# ScouseTom_CS_Shield.net
KiCad netlist of a schematic drawn in EAGLE
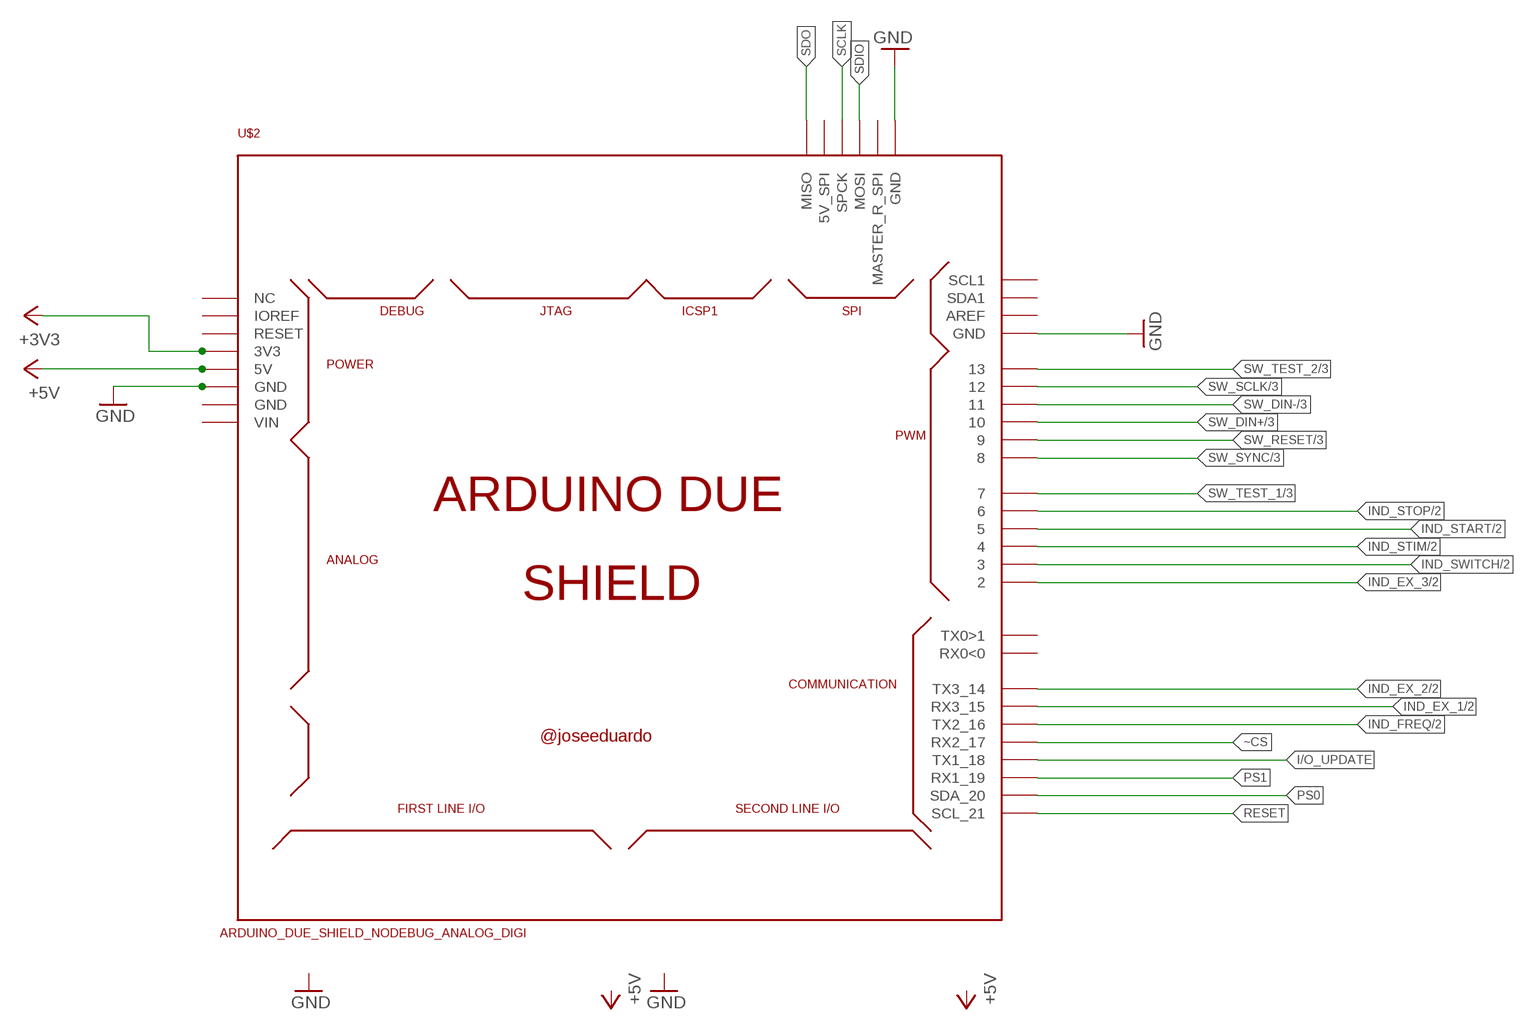
[diagram p0: schematic, sheet 1]
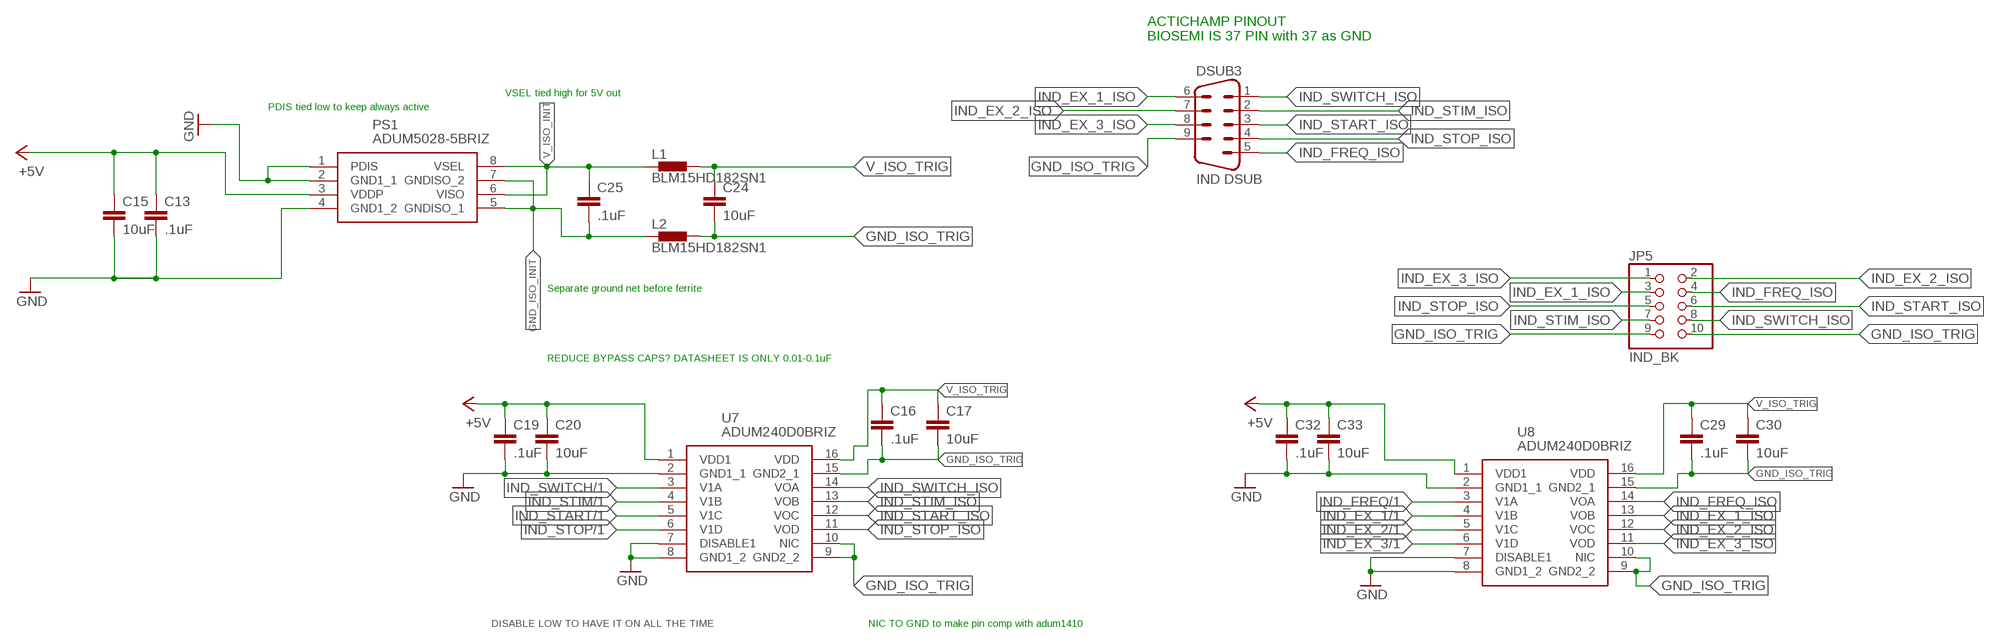
[diagram p1: schematic, sheet 2]
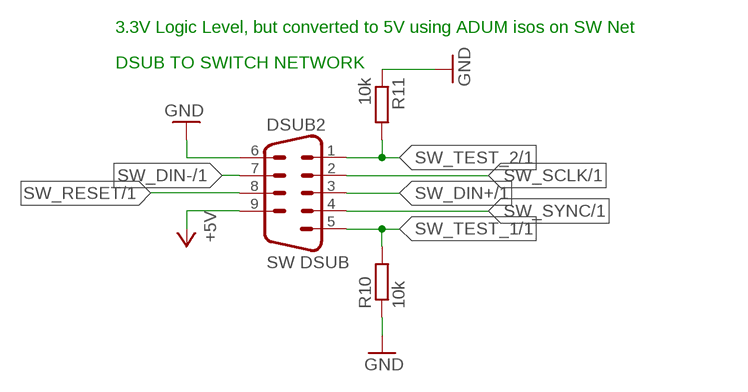
[diagram p2: schematic, sheet 3]
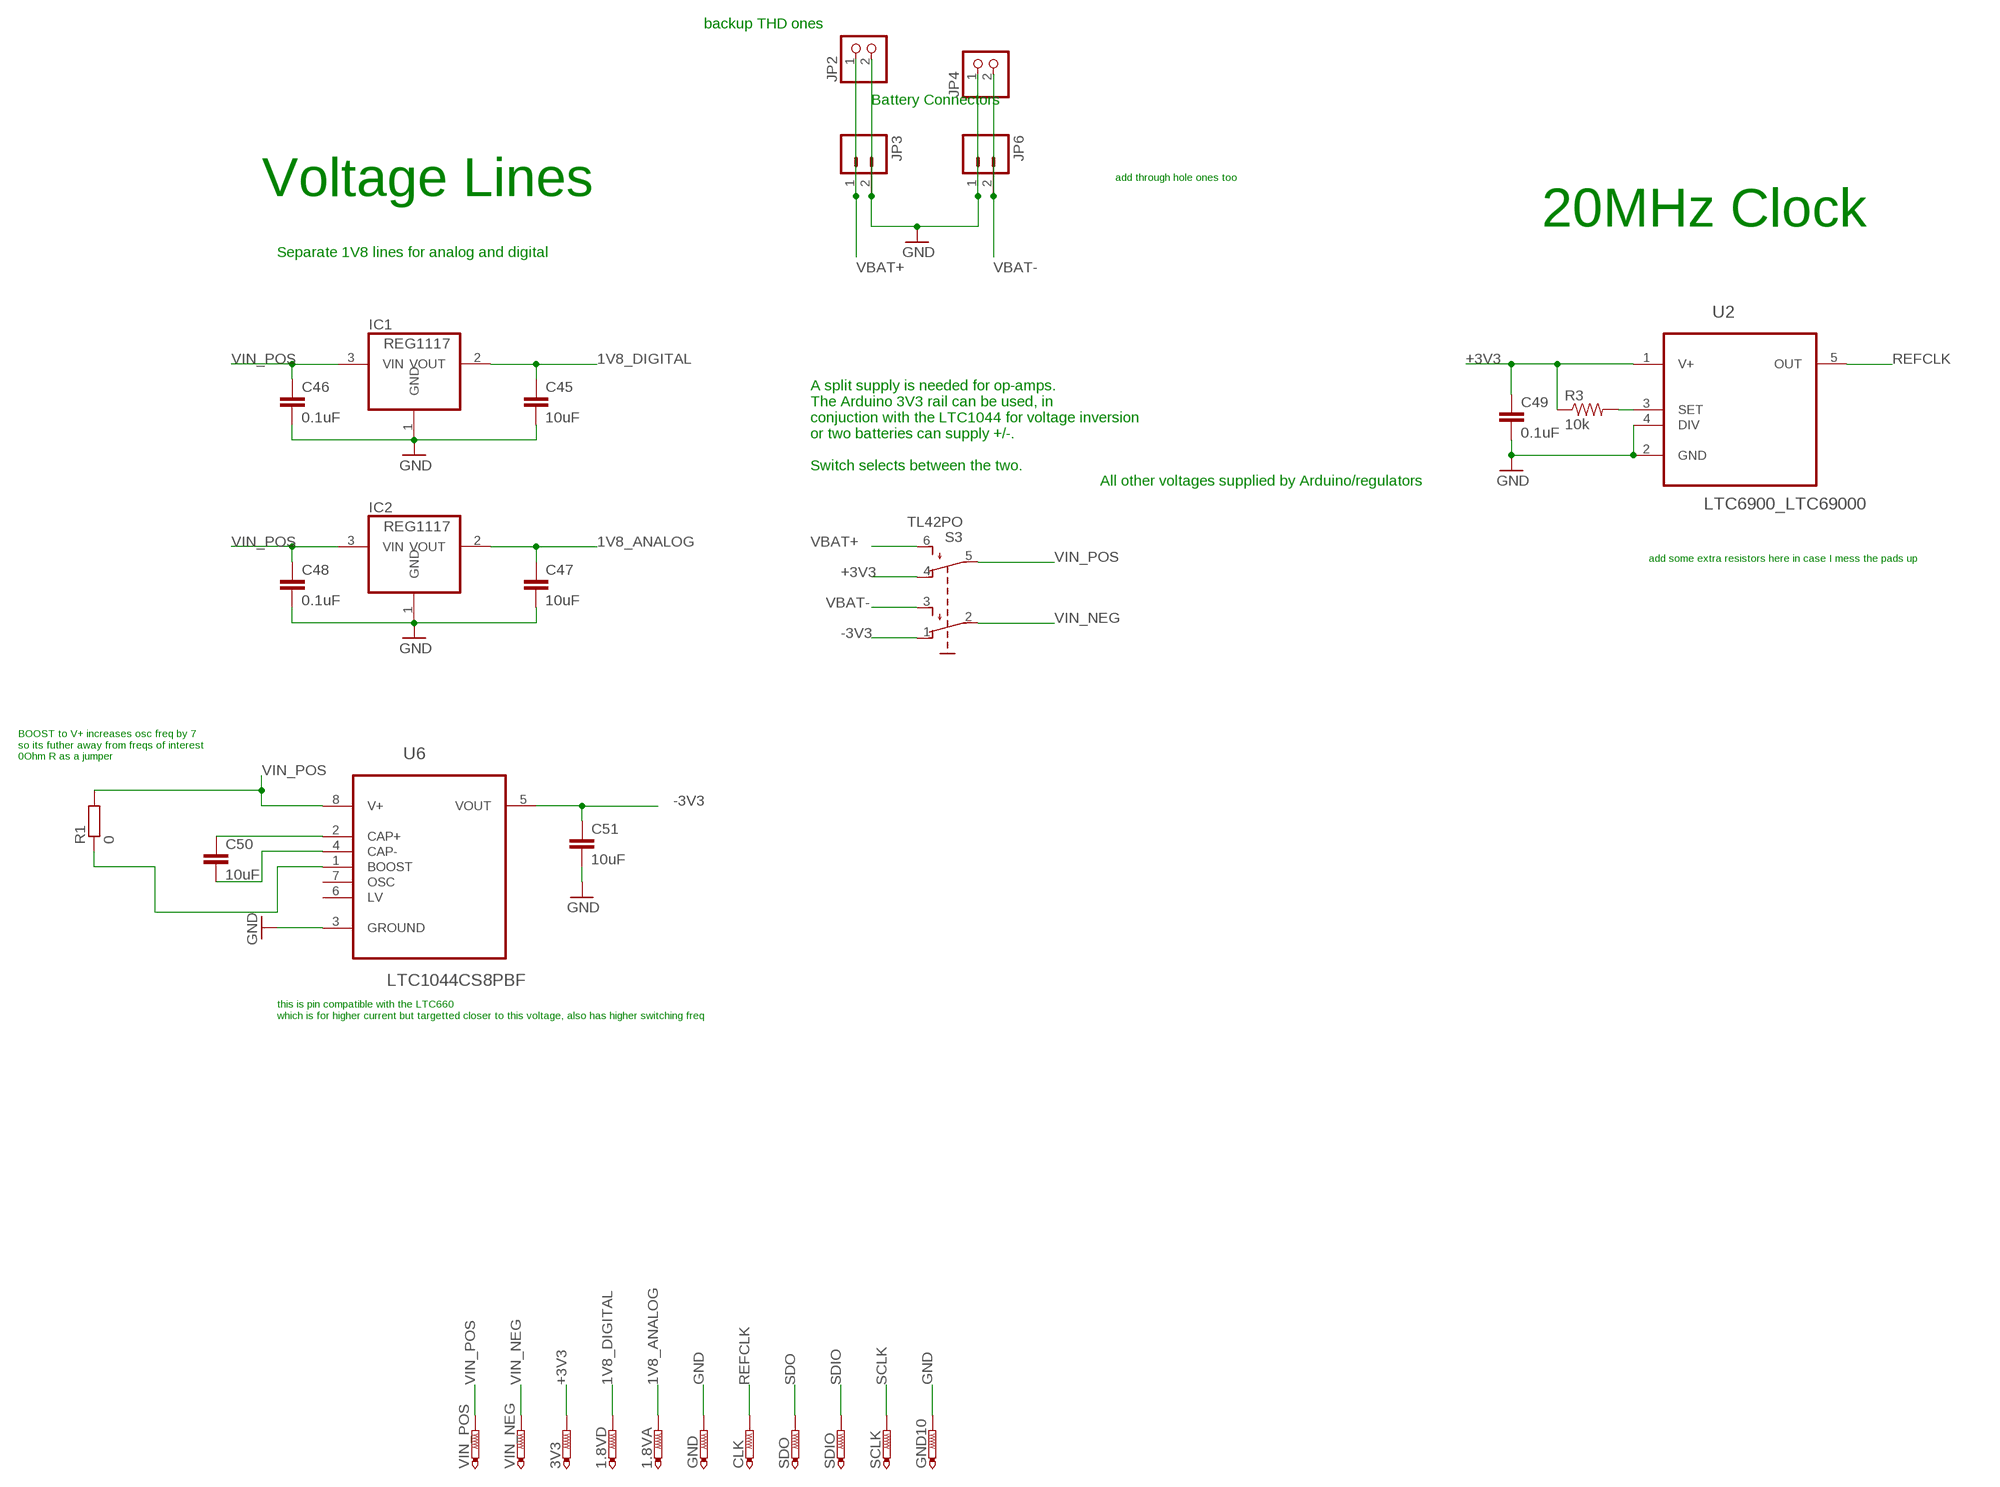
[diagram p3: schematic, sheet 4]
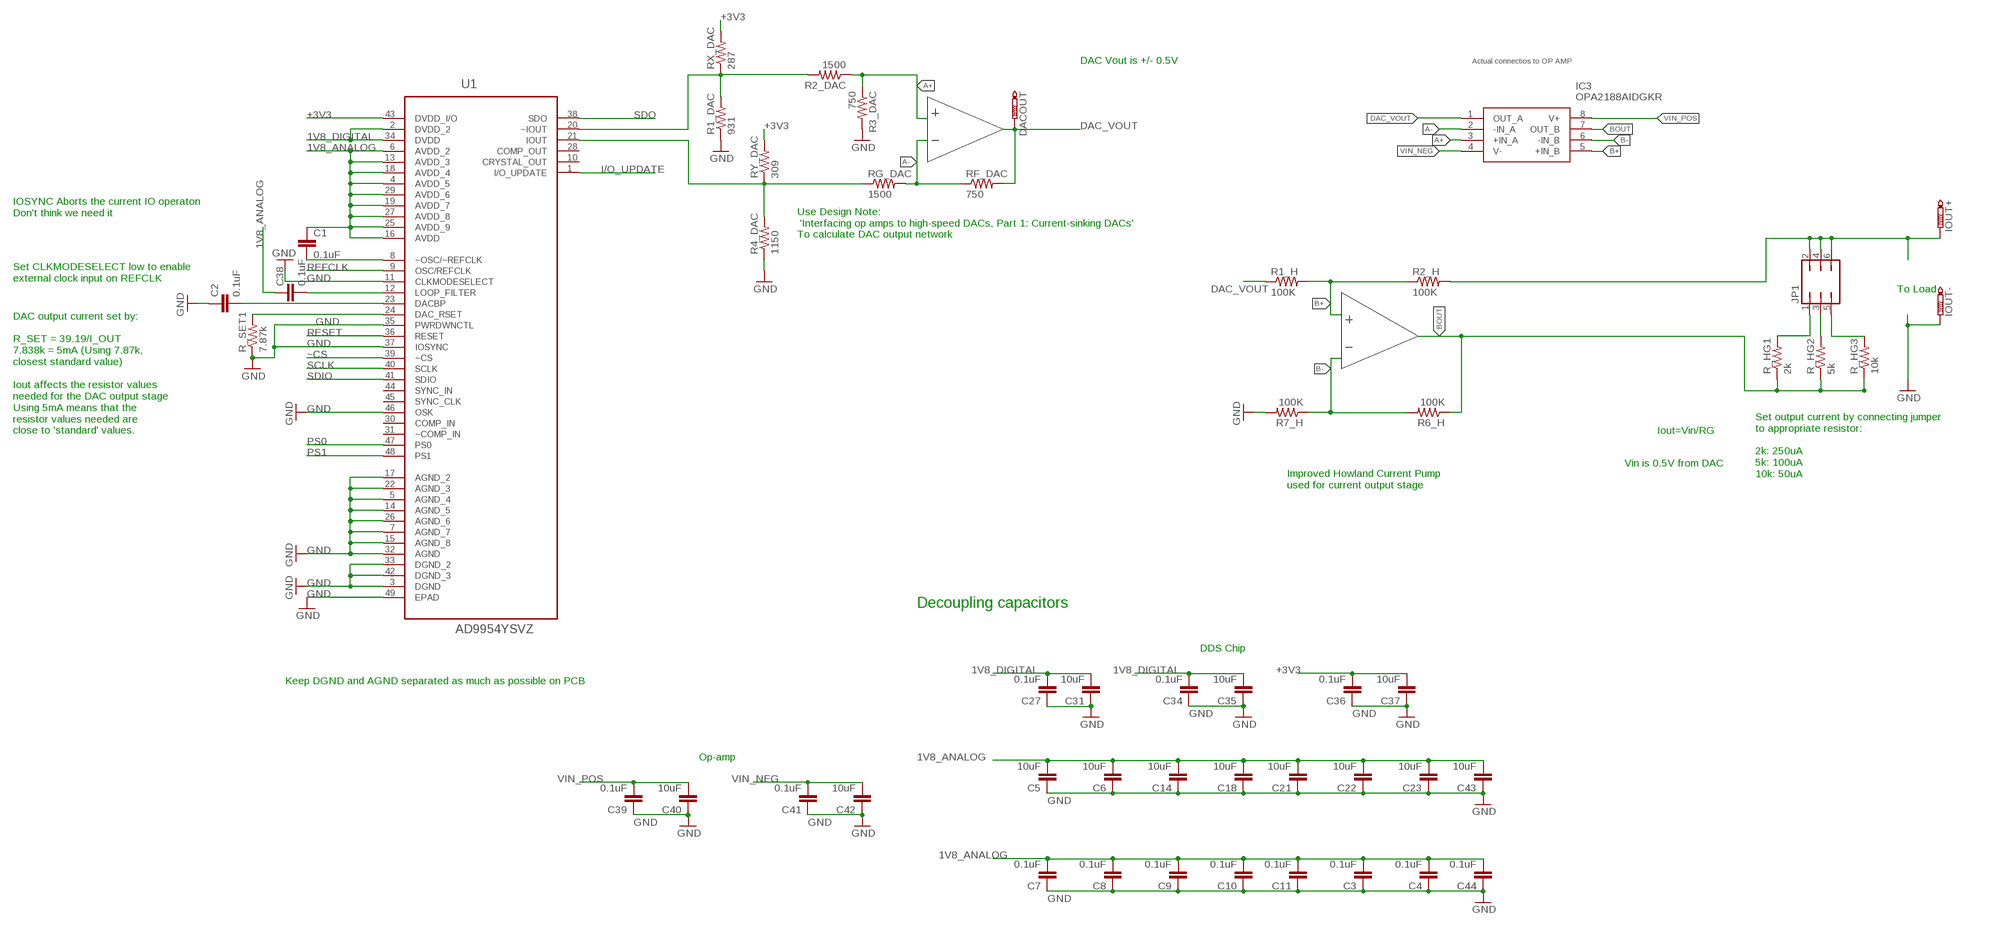
[diagram p4: schematic, sheet 5]

(export (version "E")
  (design (tool "Eeschema 10.0.6"))
  (components
    (comp (ref "U$2")
      (value "ARDUINO_DUE_SHIELD_NODEBUG_ANALOG_DIGI")
      (footprint "eagle-import:ARDUINO_DUE_SHIELD_NODEBUG_ANALOG_DIG")
      (libsource (lib "eagle-import") (part "ARDUINO_DUE_SHIELD_NODEBUG_ANALOG_DIGI"))
    )
    (comp (ref "C13")
      (value ".1uF")
      (footprint "eagle-import:C0603")
      (libsource (lib "eagle-import") (part "C-EUC0603"))
    )
    (comp (ref "C15")
      (value "10uF")
      (footprint "eagle-import:C0603")
      (libsource (lib "eagle-import") (part "C-EUC0603"))
    )
    (comp (ref "C16")
      (value ".1uF")
      (footprint "eagle-import:C0603")
      (libsource (lib "eagle-import") (part "C-EUC0603"))
    )
    (comp (ref "C17")
      (value "10uF")
      (footprint "eagle-import:C0603")
      (libsource (lib "eagle-import") (part "C-EUC0603"))
    )
    (comp (ref "C19")
      (value ".1uF")
      (footprint "eagle-import:C0603")
      (libsource (lib "eagle-import") (part "C-EUC0603"))
    )
    (comp (ref "C20")
      (value "10uF")
      (footprint "eagle-import:C0603")
      (libsource (lib "eagle-import") (part "C-EUC0603"))
    )
    (comp (ref "C24")
      (value "10uF")
      (footprint "eagle-import:C0603")
      (libsource (lib "eagle-import") (part "C-EUC0603"))
    )
    (comp (ref "C25")
      (value ".1uF")
      (footprint "eagle-import:C0603")
      (libsource (lib "eagle-import") (part "C-EUC0603"))
    )
    (comp (ref "C29")
      (value ".1uF")
      (footprint "eagle-import:C0603")
      (libsource (lib "eagle-import") (part "C-EUC0603"))
    )
    (comp (ref "C30")
      (value "10uF")
      (footprint "eagle-import:C0603")
      (libsource (lib "eagle-import") (part "C-EUC0603"))
    )
    (comp (ref "C32")
      (value ".1uF")
      (footprint "eagle-import:C0603")
      (libsource (lib "eagle-import") (part "C-EUC0603"))
    )
    (comp (ref "C33")
      (value "10uF")
      (footprint "eagle-import:C0603")
      (libsource (lib "eagle-import") (part "C-EUC0603"))
    )
    (comp (ref "DSUB3")
      (value "IND DSUB")
      (footprint "eagle-import:DSUB9")
      (libsource (lib "eagle-import") (part "ScouseTom_New_DSUB9RA"))
    )
    (comp (ref "JP5")
      (value "IND_BK")
      (footprint "eagle-import:2X05")
      (libsource (lib "eagle-import") (part "PINHD-2X5"))
    )
    (comp (ref "L1")
      (value "BLM15HD182SN1")
      (footprint "eagle-import:0402")
      (libsource (lib "eagle-import") (part "BLM15HD182SN1"))
    )
    (comp (ref "L2")
      (value "BLM15HD182SN1")
      (footprint "eagle-import:0402")
      (libsource (lib "eagle-import") (part "BLM15HD182SN1"))
    )
    (comp (ref "PS1")
      (value "ADUM5028-5BRIZ")
      (footprint "eagle-import:SOIC127P1031X265-8N")
      (fields (field (name "MOUSER_PART_NUMBER") "584-ADUM5028-5BRIZ"))
      (libsource (lib "eagle-import") (part "ADUM5028-5BRIZ"))
    )
    (comp (ref "U7")
      (value "ADUM240D0BRIZ")
      (footprint "eagle-import:SOIC127P1032X265-16N")
      (libsource (lib "eagle-import") (part "ADUM240D0BRIZ"))
    )
    (comp (ref "U8")
      (value "ADUM240D0BRIZ")
      (footprint "eagle-import:SOIC127P1032X265-16N")
      (libsource (lib "eagle-import") (part "ADUM240D0BRIZ"))
    )
    (comp (ref "C1")
      (value "0.1uF")
      (footprint "eagle-import:C0603")
      (libsource (lib "eagle-import") (part "C-EUC0603"))
    )
    (comp (ref "C2")
      (value "0.1uF")
      (footprint "eagle-import:C0603")
      (libsource (lib "eagle-import") (part "C-EUC0603"))
    )
    (comp (ref "C3")
      (value "0.1uF")
      (footprint "eagle-import:C0603")
      (libsource (lib "eagle-import") (part "C-EUC0603"))
    )
    (comp (ref "C4")
      (value "0.1uF")
      (footprint "eagle-import:C0603")
      (libsource (lib "eagle-import") (part "C-EUC0603"))
    )
    (comp (ref "C5")
      (value "10uF")
      (footprint "eagle-import:C0603")
      (libsource (lib "eagle-import") (part "C-EUC0603"))
    )
    (comp (ref "C6")
      (value "10uF")
      (footprint "eagle-import:C0603")
      (libsource (lib "eagle-import") (part "C-EUC0603"))
    )
    (comp (ref "C7")
      (value "0.1uF")
      (footprint "eagle-import:C0603")
      (libsource (lib "eagle-import") (part "C-EUC0603"))
    )
    (comp (ref "C8")
      (value "0.1uF")
      (footprint "eagle-import:C0603")
      (libsource (lib "eagle-import") (part "C-EUC0603"))
    )
    (comp (ref "C9")
      (value "0.1uF")
      (footprint "eagle-import:C0603")
      (libsource (lib "eagle-import") (part "C-EUC0603"))
    )
    (comp (ref "C10")
      (value "0.1uF")
      (footprint "eagle-import:C0603")
      (libsource (lib "eagle-import") (part "C-EUC0603"))
    )
    (comp (ref "C11")
      (value "0.1uF")
      (footprint "eagle-import:C0603")
      (libsource (lib "eagle-import") (part "C-EUC0603"))
    )
    (comp (ref "C14")
      (value "10uF")
      (footprint "eagle-import:C0603")
      (libsource (lib "eagle-import") (part "C-EUC0603"))
    )
    (comp (ref "C18")
      (value "10uF")
      (footprint "eagle-import:C0603")
      (libsource (lib "eagle-import") (part "C-EUC0603"))
    )
    (comp (ref "C21")
      (value "10uF")
      (footprint "eagle-import:C0603")
      (libsource (lib "eagle-import") (part "C-EUC0603"))
    )
    (comp (ref "C22")
      (value "10uF")
      (footprint "eagle-import:C0603")
      (libsource (lib "eagle-import") (part "C-EUC0603"))
    )
    (comp (ref "C23")
      (value "10uF")
      (footprint "eagle-import:C0603")
      (libsource (lib "eagle-import") (part "C-EUC0603"))
    )
    (comp (ref "C27")
      (value "0.1uF")
      (footprint "eagle-import:C0603")
      (libsource (lib "eagle-import") (part "C-EUC0603"))
    )
    (comp (ref "C31")
      (value "10uF")
      (footprint "eagle-import:C0603")
      (libsource (lib "eagle-import") (part "C-EUC0603"))
    )
    (comp (ref "C34")
      (value "0.1uF")
      (footprint "eagle-import:C0603")
      (libsource (lib "eagle-import") (part "C-EUC0603"))
    )
    (comp (ref "C35")
      (value "10uF")
      (footprint "eagle-import:C0603")
      (libsource (lib "eagle-import") (part "C-EUC0603"))
    )
    (comp (ref "C36")
      (value "0.1uF")
      (footprint "eagle-import:C0603")
      (libsource (lib "eagle-import") (part "C-EUC0603"))
    )
    (comp (ref "C37")
      (value "10uF")
      (footprint "eagle-import:C0603")
      (libsource (lib "eagle-import") (part "C-EUC0603"))
    )
    (comp (ref "C38")
      (value "0.1uF")
      (footprint "eagle-import:C0603")
      (libsource (lib "eagle-import") (part "C-EUC0603"))
    )
    (comp (ref "C39")
      (value "0.1uF")
      (footprint "eagle-import:C0603")
      (libsource (lib "eagle-import") (part "C-EUC0603"))
    )
    (comp (ref "C40")
      (value "10uF")
      (footprint "eagle-import:C0603")
      (libsource (lib "eagle-import") (part "C-EUC0603"))
    )
    (comp (ref "C41")
      (value "0.1uF")
      (footprint "eagle-import:C0603")
      (libsource (lib "eagle-import") (part "C-EUC0603"))
    )
    (comp (ref "C42")
      (value "10uF")
      (footprint "eagle-import:C0603")
      (libsource (lib "eagle-import") (part "C-EUC0603"))
    )
    (comp (ref "C43")
      (value "10uF")
      (footprint "eagle-import:C0603")
      (libsource (lib "eagle-import") (part "C-EUC0603"))
    )
    (comp (ref "C44")
      (value "0.1uF")
      (footprint "eagle-import:C0603")
      (libsource (lib "eagle-import") (part "C-EUC0603"))
    )
    (comp (ref "DACOUT")
      (value "PTR1PAD1-13")
      (footprint "eagle-import:P1-13")
      (libsource (lib "eagle-import") (part "PTR1PAD1-13"))
    )
    (comp (ref "IC3")
      (value "OPA2188AIDGKR")
      (footprint "eagle-import:SOP65P490X110-8N")
      (libsource (lib "eagle-import") (part "OPA2188AIDGKR"))
    )
    (comp (ref "IOUT+")
      (value "PTR1PAD1-13")
      (footprint "eagle-import:P1-13")
      (libsource (lib "eagle-import") (part "PTR1PAD1-13"))
    )
    (comp (ref "IOUT-")
      (value "PTR1PAD1-13")
      (footprint "eagle-import:P1-13")
      (libsource (lib "eagle-import") (part "PTR1PAD1-13"))
    )
    (comp (ref "JP1")
      (value "JP3Q")
      (footprint "eagle-import:JP3Q")
      (libsource (lib "eagle-import") (part "JP3Q"))
    )
    (comp (ref "R1_DAC")
      (value "931")
      (footprint "eagle-import:R0805")
      (libsource (lib "eagle-import") (part "R-US_R0805"))
    )
    (comp (ref "R1_H")
      (value "100K")
      (footprint "eagle-import:R0805")
      (libsource (lib "eagle-import") (part "R-US_R0805"))
    )
    (comp (ref "R2_DAC")
      (value "1500")
      (footprint "eagle-import:R0805")
      (libsource (lib "eagle-import") (part "R-US_R0805"))
    )
    (comp (ref "R2_H")
      (value "100K")
      (footprint "eagle-import:R0805")
      (libsource (lib "eagle-import") (part "R-US_R0805"))
    )
    (comp (ref "R3_DAC")
      (value "750")
      (footprint "eagle-import:R0805")
      (libsource (lib "eagle-import") (part "R-US_R0805"))
    )
    (comp (ref "R4_DAC")
      (value "1150")
      (footprint "eagle-import:R0805")
      (libsource (lib "eagle-import") (part "R-US_R0805"))
    )
    (comp (ref "R6_H")
      (value "100K")
      (footprint "eagle-import:R0805")
      (libsource (lib "eagle-import") (part "R-US_R0805"))
    )
    (comp (ref "R7_H")
      (value "100K")
      (footprint "eagle-import:R0805")
      (libsource (lib "eagle-import") (part "R-US_R0805"))
    )
    (comp (ref "RF_DAC")
      (value "750")
      (footprint "eagle-import:R0805")
      (libsource (lib "eagle-import") (part "R-US_R0805"))
    )
    (comp (ref "RG_DAC")
      (value "1500")
      (footprint "eagle-import:R0805")
      (libsource (lib "eagle-import") (part "R-US_R0805"))
    )
    (comp (ref "RX_DAC")
      (value "287")
      (footprint "eagle-import:R0805")
      (libsource (lib "eagle-import") (part "R-US_R0805"))
    )
    (comp (ref "RY_DAC")
      (value "309")
      (footprint "eagle-import:R0805")
      (libsource (lib "eagle-import") (part "R-US_R0805"))
    )
    (comp (ref "R_HG1")
      (value "2k")
      (footprint "eagle-import:R0805")
      (libsource (lib "eagle-import") (part "R-US_R0805"))
    )
    (comp (ref "R_HG2")
      (value "5k")
      (footprint "eagle-import:R0805")
      (libsource (lib "eagle-import") (part "R-US_R0805"))
    )
    (comp (ref "R_HG3")
      (value "10k")
      (footprint "eagle-import:R0805")
      (libsource (lib "eagle-import") (part "R-US_R0805"))
    )
    (comp (ref "R_SET1")
      (value "7.87k")
      (footprint "eagle-import:R0805")
      (libsource (lib "eagle-import") (part "R-US_R0805"))
    )
    (comp (ref "U1")
      (value "AD9954YSVZ")
      (footprint "eagle-import:QFP50P900X900X120-49N")
      (libsource (lib "eagle-import") (part "AD9954YSVZ"))
    )
    (comp (ref "DSUB2")
      (value "SW DSUB")
      (footprint "eagle-import:DSUB9")
      (libsource (lib "eagle-import") (part "DSUB9RA"))
    )
    (comp (ref "R10")
      (value "10k")
      (footprint "eagle-import:R0805")
      (libsource (lib "eagle-import") (part "R-EU_R0805"))
    )
    (comp (ref "R11")
      (value "10k")
      (footprint "eagle-import:R0805")
      (libsource (lib "eagle-import") (part "R-EU_R0805"))
    )
    (comp (ref "1.8VA")
      (value "PTR1PAD1-13")
      (footprint "eagle-import:P1-13")
      (libsource (lib "eagle-import") (part "PTR1PAD1-13"))
    )
    (comp (ref "1.8VD")
      (value "PTR1PAD1-13")
      (footprint "eagle-import:P1-13")
      (libsource (lib "eagle-import") (part "PTR1PAD1-13"))
    )
    (comp (ref "3V3")
      (value "PTR1PAD1-13")
      (footprint "eagle-import:P1-13")
      (libsource (lib "eagle-import") (part "PTR1PAD1-13"))
    )
    (comp (ref "C45")
      (value "10uF")
      (footprint "eagle-import:C0603")
      (libsource (lib "eagle-import") (part "C-EUC0603"))
    )
    (comp (ref "C46")
      (value "0.1uF")
      (footprint "eagle-import:C0603")
      (libsource (lib "eagle-import") (part "C-EUC0603"))
    )
    (comp (ref "C47")
      (value "10uF")
      (footprint "eagle-import:C0603")
      (libsource (lib "eagle-import") (part "C-EUC0603"))
    )
    (comp (ref "C48")
      (value "0.1uF")
      (footprint "eagle-import:C0603")
      (libsource (lib "eagle-import") (part "C-EUC0603"))
    )
    (comp (ref "C49")
      (value "0.1uF")
      (footprint "eagle-import:C0603")
      (libsource (lib "eagle-import") (part "C-EUC0603"))
    )
    (comp (ref "C50")
      (value "10uF")
      (footprint "eagle-import:C0603")
      (libsource (lib "eagle-import") (part "C-EUC0603"))
    )
    (comp (ref "C51")
      (value "10uF")
      (footprint "eagle-import:C0603")
      (libsource (lib "eagle-import") (part "C-EUC0603"))
    )
    (comp (ref "CLK")
      (value "PTR1PAD1-13")
      (footprint "eagle-import:P1-13")
      (libsource (lib "eagle-import") (part "PTR1PAD1-13"))
    )
    (comp (ref "GND")
      (value "PTR1PAD1-13")
      (footprint "eagle-import:P1-13")
      (libsource (lib "eagle-import") (part "PTR1PAD1-13"))
    )
    (comp (ref "GND10")
      (value "PTR1PAD1-13")
      (footprint "eagle-import:P1-13")
      (libsource (lib "eagle-import") (part "PTR1PAD1-13"))
    )
    (comp (ref "IC1")
      (value "REG1117")
      (footprint "eagle-import:SOT223")
      (libsource (lib "eagle-import") (part "REG1117"))
    )
    (comp (ref "IC2")
      (value "REG1117")
      (footprint "eagle-import:SOT223")
      (libsource (lib "eagle-import") (part "REG1117"))
    )
    (comp (ref "JP2")
      (value "PINHD-1X2")
      (footprint "eagle-import:1X02")
      (libsource (lib "eagle-import") (part "PINHD-1X2"))
    )
    (comp (ref "JP3")
      (value "M02-JST-2MM-SMT")
      (footprint "eagle-import:JST-2-SMD")
      (libsource (lib "eagle-import") (part "M02-JST-2MM-SMT"))
    )
    (comp (ref "JP4")
      (value "PINHD-1X2")
      (footprint "eagle-import:1X02")
      (libsource (lib "eagle-import") (part "PINHD-1X2"))
    )
    (comp (ref "JP6")
      (value "M02-JST-2MM-SMT")
      (footprint "eagle-import:JST-2-SMD")
      (libsource (lib "eagle-import") (part "M02-JST-2MM-SMT"))
    )
    (comp (ref "R1")
      (value "0")
      (footprint "eagle-import:R0805")
      (libsource (lib "eagle-import") (part "R-EU_R0805"))
    )
    (comp (ref "R3")
      (value "10k")
      (footprint "eagle-import:R0805")
      (libsource (lib "eagle-import") (part "R-US_R0805"))
    )
    (comp (ref "S3")
      (value "TL42PO")
      (footprint "eagle-import:TL4XPO")
      (libsource (lib "eagle-import") (part "TL42PO"))
    )
    (comp (ref "SCLK")
      (value "PTR1PAD1-13")
      (footprint "eagle-import:P1-13")
      (libsource (lib "eagle-import") (part "PTR1PAD1-13"))
    )
    (comp (ref "SDIO")
      (value "PTR1PAD1-13")
      (footprint "eagle-import:P1-13")
      (libsource (lib "eagle-import") (part "PTR1PAD1-13"))
    )
    (comp (ref "SDO")
      (value "PTR1PAD1-13")
      (footprint "eagle-import:P1-13")
      (libsource (lib "eagle-import") (part "PTR1PAD1-13"))
    )
    (comp (ref "U2")
      (value "LTC6900_LTC69000")
      (footprint "eagle-import:LTC6900_SOT23-5L")
      (libsource (lib "eagle-import") (part "LTC6900_LTC69000"))
    )
    (comp (ref "U6")
      (value "LTC1044CS8PBF")
      (footprint "eagle-import:SOIC127P600X175-8N")
      (fields (field (name "MPN") "LTC1044CS8#PBF"))
      (libsource (lib "eagle-import") (part "LTC1044CS8PBF"))
    )
    (comp (ref "VIN_NEG")
      (value "PTR1PAD1-13")
      (footprint "eagle-import:P1-13")
      (libsource (lib "eagle-import") (part "PTR1PAD1-13"))
    )
    (comp (ref "VIN_POS")
      (value "PTR1PAD1-13")
      (footprint "eagle-import:P1-13")
      (libsource (lib "eagle-import") (part "PTR1PAD1-13"))
    )
  )
  (nets
    (net (code "1") (name "+3V3") (class "Default")
      (node (ref "3V3") (pin "TP") (pinfunction "TP_TP") (pintype "input"))
      (node (ref "C36") (pin "2") (pinfunction "2_2") (pintype "passive"))
      (node (ref "C37") (pin "2") (pinfunction "2_2") (pintype "passive"))
      (node (ref "C49") (pin "1") (pinfunction "1_1") (pintype "passive"))
      (node (ref "R3") (pin "1") (pinfunction "1_1") (pintype "passive"))
      (node (ref "RX_DAC") (pin "2") (pinfunction "2_2") (pintype "passive"))
      (node (ref "RY_DAC") (pin "2") (pinfunction "2_2") (pintype "passive"))
      (node (ref "S3") (pin "4") (pinfunction "O1_4") (pintype "passive"))
      (node (ref "U$2") (pin "3V3") (pinfunction "3V3_3V3") (pintype "bidirectional"))
      (node (ref "U1") (pin "43") (pinfunction "DVDD_I/O_43") (pintype "power_in"))
      (node (ref "U2") (pin "1") (pinfunction "V+_1") (pintype "power_in"))
    )
    (net (code "2") (name "+5V") (class "Default")
      (node (ref "C13") (pin "1") (pinfunction "1_1") (pintype "passive"))
      (node (ref "C15") (pin "1") (pinfunction "1_1") (pintype "passive"))
      (node (ref "C19") (pin "1") (pinfunction "1_1") (pintype "passive"))
      (node (ref "C20") (pin "1") (pinfunction "1_1") (pintype "passive"))
      (node (ref "C32") (pin "1") (pinfunction "1_1") (pintype "passive"))
      (node (ref "C33") (pin "1") (pinfunction "1_1") (pintype "passive"))
      (node (ref "DSUB2") (pin "9") (pinfunction "9_9") (pintype "passive"))
      (node (ref "PS1") (pin "3") (pinfunction "VDDP_3") (pintype "bidirectional"))
      (node (ref "U$2") (pin "5V0") (pinfunction "5V_5V0") (pintype "bidirectional"))
      (node (ref "U7") (pin "1") (pinfunction "VDD1_1") (pintype "power_in"))
      (node (ref "U8") (pin "1") (pinfunction "VDD1_1") (pintype "power_in"))
    )
    (net (code "3") (name "-3V3") (class "Default")
      (node (ref "C51") (pin "1") (pinfunction "1_1") (pintype "passive"))
      (node (ref "S3") (pin "1") (pinfunction "O_1") (pintype "passive"))
      (node (ref "U6") (pin "5") (pinfunction "VOUT_5") (pintype "output"))
    )
    (net (code "4") (name "1V8_ANALOG") (class "Default")
      (node (ref "1.8VA") (pin "TP") (pinfunction "TP_TP") (pintype "input"))
      (node (ref "C1") (pin "1") (pinfunction "1_1") (pintype "passive"))
      (node (ref "C10") (pin "2") (pinfunction "2_2") (pintype "passive"))
      (node (ref "C11") (pin "2") (pinfunction "2_2") (pintype "passive"))
      (node (ref "C14") (pin "2") (pinfunction "2_2") (pintype "passive"))
      (node (ref "C18") (pin "2") (pinfunction "2_2") (pintype "passive"))
      (node (ref "C21") (pin "2") (pinfunction "2_2") (pintype "passive"))
      (node (ref "C22") (pin "2") (pinfunction "2_2") (pintype "passive"))
      (node (ref "C23") (pin "2") (pinfunction "2_2") (pintype "passive"))
      (node (ref "C3") (pin "2") (pinfunction "2_2") (pintype "passive"))
      (node (ref "C38") (pin "1") (pinfunction "1_1") (pintype "passive"))
      (node (ref "C4") (pin "2") (pinfunction "2_2") (pintype "passive"))
      (node (ref "C43") (pin "2") (pinfunction "2_2") (pintype "passive"))
      (node (ref "C44") (pin "2") (pinfunction "2_2") (pintype "passive"))
      (node (ref "C47") (pin "1") (pinfunction "1_1") (pintype "passive"))
      (node (ref "C5") (pin "2") (pinfunction "2_2") (pintype "passive"))
      (node (ref "C6") (pin "2") (pinfunction "2_2") (pintype "passive"))
      (node (ref "C7") (pin "2") (pinfunction "2_2") (pintype "passive"))
      (node (ref "C8") (pin "2") (pinfunction "2_2") (pintype "passive"))
      (node (ref "C9") (pin "2") (pinfunction "2_2") (pintype "passive"))
      (node (ref "IC2") (pin "2") (pinfunction "VOUT_2") (pintype "output"))
      (node (ref "U1") (pin "13") (pinfunction "AVDD_3_13") (pintype "power_in"))
      (node (ref "U1") (pin "16") (pinfunction "AVDD_16") (pintype "power_in"))
      (node (ref "U1") (pin "18") (pinfunction "AVDD_4_18") (pintype "power_in"))
      (node (ref "U1") (pin "19") (pinfunction "AVDD_7_19") (pintype "power_in"))
      (node (ref "U1") (pin "25") (pinfunction "AVDD_9_25") (pintype "power_in"))
      (node (ref "U1") (pin "27") (pinfunction "AVDD_8_27") (pintype "power_in"))
      (node (ref "U1") (pin "29") (pinfunction "AVDD_6_29") (pintype "power_in"))
      (node (ref "U1") (pin "4") (pinfunction "AVDD_5_4") (pintype "power_in"))
      (node (ref "U1") (pin "6") (pinfunction "AVDD_2_6") (pintype "power_in"))
    )
    (net (code "5") (name "1V8_DIGITAL") (class "Default")
      (node (ref "1.8VD") (pin "TP") (pinfunction "TP_TP") (pintype "input"))
      (node (ref "C27") (pin "2") (pinfunction "2_2") (pintype "passive"))
      (node (ref "C31") (pin "2") (pinfunction "2_2") (pintype "passive"))
      (node (ref "C34") (pin "2") (pinfunction "2_2") (pintype "passive"))
      (node (ref "C35") (pin "2") (pinfunction "2_2") (pintype "passive"))
      (node (ref "C45") (pin "1") (pinfunction "1_1") (pintype "passive"))
      (node (ref "IC1") (pin "2") (pinfunction "VOUT_2") (pintype "output"))
      (node (ref "U1") (pin "2") (pinfunction "DVDD_2_2") (pintype "power_in"))
      (node (ref "U1") (pin "34") (pinfunction "DVDD_34") (pintype "power_in"))
    )
    (net (code "6") (name "A+") (class "Default")
      (node (ref "IC3") (pin "3") (pinfunction "+IN_A_3") (pintype "input"))
      (node (ref "R2_DAC") (pin "1") (pinfunction "1_1") (pintype "passive"))
      (node (ref "R3_DAC") (pin "1") (pinfunction "1_1") (pintype "passive"))
    )
    (net (code "7") (name "A-") (class "Default")
      (node (ref "IC3") (pin "2") (pinfunction "-IN_A_2") (pintype "input"))
      (node (ref "RF_DAC") (pin "1") (pinfunction "1_1") (pintype "passive"))
      (node (ref "RG_DAC") (pin "2") (pinfunction "2_2") (pintype "passive"))
    )
    (net (code "8") (name "B+") (class "Default")
      (node (ref "IC3") (pin "5") (pinfunction "+IN_B_5") (pintype "input"))
      (node (ref "R1_H") (pin "2") (pinfunction "2_2") (pintype "passive"))
      (node (ref "R2_H") (pin "1") (pinfunction "1_1") (pintype "passive"))
    )
    (net (code "9") (name "B-") (class "Default")
      (node (ref "IC3") (pin "6") (pinfunction "-IN_B_6") (pintype "input"))
      (node (ref "R6_H") (pin "2") (pinfunction "2_2") (pintype "passive"))
      (node (ref "R7_H") (pin "1") (pinfunction "1_1") (pintype "passive"))
    )
    (net (code "10") (name "BOUT") (class "Default")
      (node (ref "IC3") (pin "7") (pinfunction "OUT_B_7") (pintype "output"))
      (node (ref "R6_H") (pin "1") (pinfunction "1_1") (pintype "passive"))
      (node (ref "R_HG1") (pin "1") (pinfunction "1_1") (pintype "passive"))
      (node (ref "R_HG2") (pin "1") (pinfunction "1_1") (pintype "passive"))
      (node (ref "R_HG3") (pin "1") (pinfunction "1_1") (pintype "passive"))
    )
    (net (code "11") (name "DAC_VOUT") (class "Default")
      (node (ref "DACOUT") (pin "TP") (pinfunction "TP_TP") (pintype "input"))
      (node (ref "IC3") (pin "1") (pinfunction "OUT_A_1") (pintype "output"))
      (node (ref "R1_H") (pin "1") (pinfunction "1_1") (pintype "passive"))
      (node (ref "RF_DAC") (pin "2") (pinfunction "2_2") (pintype "passive"))
    )
    (net (code "12") (name "GND") (class "Default")
      (node (ref "C10") (pin "1") (pinfunction "1_1") (pintype "passive"))
      (node (ref "C11") (pin "1") (pinfunction "1_1") (pintype "passive"))
      (node (ref "C13") (pin "2") (pinfunction "2_2") (pintype "passive"))
      (node (ref "C14") (pin "1") (pinfunction "1_1") (pintype "passive"))
      (node (ref "C15") (pin "2") (pinfunction "2_2") (pintype "passive"))
      (node (ref "C18") (pin "1") (pinfunction "1_1") (pintype "passive"))
      (node (ref "C19") (pin "2") (pinfunction "2_2") (pintype "passive"))
      (node (ref "C2") (pin "1") (pinfunction "1_1") (pintype "passive"))
      (node (ref "C20") (pin "2") (pinfunction "2_2") (pintype "passive"))
      (node (ref "C21") (pin "1") (pinfunction "1_1") (pintype "passive"))
      (node (ref "C22") (pin "1") (pinfunction "1_1") (pintype "passive"))
      (node (ref "C23") (pin "1") (pinfunction "1_1") (pintype "passive"))
      (node (ref "C27") (pin "1") (pinfunction "1_1") (pintype "passive"))
      (node (ref "C3") (pin "1") (pinfunction "1_1") (pintype "passive"))
      (node (ref "C31") (pin "1") (pinfunction "1_1") (pintype "passive"))
      (node (ref "C32") (pin "2") (pinfunction "2_2") (pintype "passive"))
      (node (ref "C33") (pin "2") (pinfunction "2_2") (pintype "passive"))
      (node (ref "C34") (pin "1") (pinfunction "1_1") (pintype "passive"))
      (node (ref "C35") (pin "1") (pinfunction "1_1") (pintype "passive"))
      (node (ref "C36") (pin "1") (pinfunction "1_1") (pintype "passive"))
      (node (ref "C37") (pin "1") (pinfunction "1_1") (pintype "passive"))
      (node (ref "C39") (pin "1") (pinfunction "1_1") (pintype "passive"))
      (node (ref "C4") (pin "1") (pinfunction "1_1") (pintype "passive"))
      (node (ref "C40") (pin "1") (pinfunction "1_1") (pintype "passive"))
      (node (ref "C41") (pin "1") (pinfunction "1_1") (pintype "passive"))
      (node (ref "C42") (pin "1") (pinfunction "1_1") (pintype "passive"))
      (node (ref "C43") (pin "1") (pinfunction "1_1") (pintype "passive"))
      (node (ref "C44") (pin "1") (pinfunction "1_1") (pintype "passive"))
      (node (ref "C45") (pin "2") (pinfunction "2_2") (pintype "passive"))
      (node (ref "C46") (pin "2") (pinfunction "2_2") (pintype "passive"))
      (node (ref "C47") (pin "2") (pinfunction "2_2") (pintype "passive"))
      (node (ref "C48") (pin "2") (pinfunction "2_2") (pintype "passive"))
      (node (ref "C49") (pin "2") (pinfunction "2_2") (pintype "passive"))
      (node (ref "C5") (pin "1") (pinfunction "1_1") (pintype "passive"))
      (node (ref "C51") (pin "2") (pinfunction "2_2") (pintype "passive"))
      (node (ref "C6") (pin "1") (pinfunction "1_1") (pintype "passive"))
      (node (ref "C7") (pin "1") (pinfunction "1_1") (pintype "passive"))
      (node (ref "C8") (pin "1") (pinfunction "1_1") (pintype "passive"))
      (node (ref "C9") (pin "1") (pinfunction "1_1") (pintype "passive"))
      (node (ref "DSUB2") (pin "6") (pinfunction "6_6") (pintype "passive"))
      (node (ref "GND") (pin "TP") (pinfunction "TP_TP") (pintype "input"))
      (node (ref "GND10") (pin "TP") (pinfunction "TP_TP") (pintype "input"))
      (node (ref "IC1") (pin "1") (pinfunction "GND_1") (pintype "power_in"))
      (node (ref "IC2") (pin "1") (pinfunction "GND_1") (pintype "power_in"))
      (node (ref "IOUT-") (pin "TP") (pinfunction "TP_TP") (pintype "input"))
      (node (ref "JP2") (pin "2") (pinfunction "2_2") (pintype "passive"))
      (node (ref "JP3") (pin "2") (pinfunction "2_2") (pintype "passive"))
      (node (ref "JP4") (pin "1") (pinfunction "1_1") (pintype "passive"))
      (node (ref "JP6") (pin "1") (pinfunction "1_1") (pintype "passive"))
      (node (ref "PS1") (pin "1") (pinfunction "PDIS_1") (pintype "bidirectional"))
      (node (ref "PS1") (pin "2") (pinfunction "GND1_1_2") (pintype "bidirectional"))
      (node (ref "PS1") (pin "4") (pinfunction "GND1_2_4") (pintype "bidirectional"))
      (node (ref "R10") (pin "1") (pinfunction "1_1") (pintype "passive"))
      (node (ref "R11") (pin "1") (pinfunction "1_1") (pintype "passive"))
      (node (ref "R1_DAC") (pin "1") (pinfunction "1_1") (pintype "passive"))
      (node (ref "R3_DAC") (pin "2") (pinfunction "2_2") (pintype "passive"))
      (node (ref "R4_DAC") (pin "1") (pinfunction "1_1") (pintype "passive"))
      (node (ref "R7_H") (pin "2") (pinfunction "2_2") (pintype "passive"))
      (node (ref "R_SET1") (pin "1") (pinfunction "1_1") (pintype "passive"))
      (node (ref "U$2") (pin "GND") (pinfunction "GND_GND") (pintype "bidirectional"))
      (node (ref "U$2") (pin "GND_4") (pinfunction "GND_GND_4") (pintype "bidirectional"))
      (node (ref "U$2") (pin "GND_5") (pinfunction "GND_GND_5") (pintype "bidirectional"))
      (node (ref "U1") (pin "11") (pinfunction "CLKMODESELECT_11") (pintype "input"))
      (node (ref "U1") (pin "14") (pinfunction "AGND_5_14") (pintype "passive"))
      (node (ref "U1") (pin "15") (pinfunction "AGND_8_15") (pintype "passive"))
      (node (ref "U1") (pin "17") (pinfunction "AGND_2_17") (pintype "passive"))
      (node (ref "U1") (pin "22") (pinfunction "AGND_3_22") (pintype "passive"))
      (node (ref "U1") (pin "26") (pinfunction "AGND_6_26") (pintype "passive"))
      (node (ref "U1") (pin "3") (pinfunction "DGND_3") (pintype "passive"))
      (node (ref "U1") (pin "32") (pinfunction "AGND_32") (pintype "passive"))
      (node (ref "U1") (pin "33") (pinfunction "DGND_2_33") (pintype "passive"))
      (node (ref "U1") (pin "35") (pinfunction "PWRDWNCTL_35") (pintype "input"))
      (node (ref "U1") (pin "37") (pinfunction "IOSYNC_37") (pintype "input"))
      (node (ref "U1") (pin "42") (pinfunction "DGND_3_42") (pintype "passive"))
      (node (ref "U1") (pin "46") (pinfunction "OSK_46") (pintype "input"))
      (node (ref "U1") (pin "49") (pinfunction "EPAD_49") (pintype "passive"))
      (node (ref "U1") (pin "5") (pinfunction "AGND_4_5") (pintype "passive"))
      (node (ref "U1") (pin "7") (pinfunction "AGND_7_7") (pintype "passive"))
      (node (ref "U2") (pin "2") (pinfunction "GND_2") (pintype "passive"))
      (node (ref "U2") (pin "4") (pinfunction "DIV_4") (pintype "input"))
      (node (ref "U6") (pin "3") (pinfunction "GROUND_3") (pintype "passive"))
      (node (ref "U7") (pin "2") (pinfunction "GND1_1_2") (pintype "power_in"))
      (node (ref "U7") (pin "7") (pinfunction "DISABLE1_7") (pintype "bidirectional"))
      (node (ref "U7") (pin "8") (pinfunction "GND1_2_8") (pintype "power_in"))
      (node (ref "U8") (pin "2") (pinfunction "GND1_1_2") (pintype "power_in"))
      (node (ref "U8") (pin "7") (pinfunction "DISABLE1_7") (pintype "bidirectional"))
      (node (ref "U8") (pin "8") (pinfunction "GND1_2_8") (pintype "power_in"))
    )
    (net (code "13") (name "GND_ISO_INIT") (class "Default")
      (node (ref "C25") (pin "2") (pinfunction "2_2") (pintype "passive"))
      (node (ref "L2") (pin "1") (pinfunction "1_1") (pintype "passive"))
      (node (ref "PS1") (pin "5") (pinfunction "GNDISO_1_5") (pintype "bidirectional"))
      (node (ref "PS1") (pin "7") (pinfunction "GNDISO_2_7") (pintype "bidirectional"))
    )
    (net (code "14") (name "GND_ISO_TRIG") (class "Default")
      (node (ref "C16") (pin "2") (pinfunction "2_2") (pintype "passive"))
      (node (ref "C17") (pin "2") (pinfunction "2_2") (pintype "passive"))
      (node (ref "C24") (pin "2") (pinfunction "2_2") (pintype "passive"))
      (node (ref "C29") (pin "2") (pinfunction "2_2") (pintype "passive"))
      (node (ref "C30") (pin "2") (pinfunction "2_2") (pintype "passive"))
      (node (ref "DSUB3") (pin "9") (pinfunction "9_9") (pintype "passive"))
      (node (ref "JP5") (pin "10") (pinfunction "10_10") (pintype "passive"))
      (node (ref "JP5") (pin "9") (pinfunction "9_9") (pintype "passive"))
      (node (ref "L2") (pin "2") (pinfunction "2_2") (pintype "passive"))
      (node (ref "U7") (pin "10") (pinfunction "NIC_10") (pintype "bidirectional"))
      (node (ref "U7") (pin "15") (pinfunction "GND2_1_15") (pintype "power_in"))
      (node (ref "U7") (pin "9") (pinfunction "GND2_2_9") (pintype "power_in"))
      (node (ref "U8") (pin "10") (pinfunction "NIC_10") (pintype "bidirectional"))
      (node (ref "U8") (pin "15") (pinfunction "GND2_1_15") (pintype "power_in"))
      (node (ref "U8") (pin "9") (pinfunction "GND2_2_9") (pintype "power_in"))
    )
    (net (code "15") (name "IND_EX_1") (class "Default")
      (node (ref "U$2") (pin "15") (pinfunction "RX3_15_15") (pintype "bidirectional"))
      (node (ref "U8") (pin "4") (pinfunction "V1B_4") (pintype "input"))
    )
    (net (code "16") (name "IND_EX_1_ISO") (class "Default")
      (node (ref "DSUB3") (pin "6") (pinfunction "6_6") (pintype "passive"))
      (node (ref "JP5") (pin "3") (pinfunction "3_3") (pintype "passive"))
      (node (ref "U8") (pin "13") (pinfunction "VOB_13") (pintype "output"))
    )
    (net (code "17") (name "IND_EX_2") (class "Default")
      (node (ref "U$2") (pin "14") (pinfunction "TX3_14_14") (pintype "bidirectional"))
      (node (ref "U8") (pin "5") (pinfunction "V1C_5") (pintype "input"))
    )
    (net (code "18") (name "IND_EX_2_ISO") (class "Default")
      (node (ref "DSUB3") (pin "7") (pinfunction "7_7") (pintype "passive"))
      (node (ref "JP5") (pin "2") (pinfunction "2_2") (pintype "passive"))
      (node (ref "U8") (pin "12") (pinfunction "VOC_12") (pintype "output"))
    )
    (net (code "19") (name "IND_EX_3") (class "Default")
      (node (ref "U$2") (pin "2") (pinfunction "2_2") (pintype "bidirectional"))
      (node (ref "U8") (pin "6") (pinfunction "V1D_6") (pintype "input"))
    )
    (net (code "20") (name "IND_EX_3_ISO") (class "Default")
      (node (ref "DSUB3") (pin "8") (pinfunction "8_8") (pintype "passive"))
      (node (ref "JP5") (pin "1") (pinfunction "1_1") (pintype "passive"))
      (node (ref "U8") (pin "11") (pinfunction "VOD_11") (pintype "output"))
    )
    (net (code "21") (name "IND_FREQ") (class "Default")
      (node (ref "U$2") (pin "16") (pinfunction "TX2_16_16") (pintype "bidirectional"))
      (node (ref "U8") (pin "3") (pinfunction "V1A_3") (pintype "input"))
    )
    (net (code "22") (name "IND_FREQ_ISO") (class "Default")
      (node (ref "DSUB3") (pin "5") (pinfunction "5_5") (pintype "passive"))
      (node (ref "JP5") (pin "4") (pinfunction "4_4") (pintype "passive"))
      (node (ref "U8") (pin "14") (pinfunction "VOA_14") (pintype "output"))
    )
    (net (code "23") (name "IND_START") (class "Default")
      (node (ref "U$2") (pin "5") (pinfunction "5_5") (pintype "bidirectional"))
      (node (ref "U7") (pin "5") (pinfunction "V1C_5") (pintype "input"))
    )
    (net (code "24") (name "IND_START_ISO") (class "Default")
      (node (ref "DSUB3") (pin "3") (pinfunction "3_3") (pintype "passive"))
      (node (ref "JP5") (pin "6") (pinfunction "6_6") (pintype "passive"))
      (node (ref "U7") (pin "12") (pinfunction "VOC_12") (pintype "output"))
    )
    (net (code "25") (name "IND_STIM") (class "Default")
      (node (ref "U$2") (pin "4") (pinfunction "4_4") (pintype "bidirectional"))
      (node (ref "U7") (pin "4") (pinfunction "V1B_4") (pintype "input"))
    )
    (net (code "26") (name "IND_STIM_ISO") (class "Default")
      (node (ref "DSUB3") (pin "2") (pinfunction "2_2") (pintype "passive"))
      (node (ref "JP5") (pin "7") (pinfunction "7_7") (pintype "passive"))
      (node (ref "U7") (pin "13") (pinfunction "VOB_13") (pintype "output"))
    )
    (net (code "27") (name "IND_STOP") (class "Default")
      (node (ref "U$2") (pin "6") (pinfunction "6_6") (pintype "bidirectional"))
      (node (ref "U7") (pin "6") (pinfunction "V1D_6") (pintype "input"))
    )
    (net (code "28") (name "IND_STOP_ISO") (class "Default")
      (node (ref "DSUB3") (pin "4") (pinfunction "4_4") (pintype "passive"))
      (node (ref "JP5") (pin "5") (pinfunction "5_5") (pintype "passive"))
      (node (ref "U7") (pin "11") (pinfunction "VOD_11") (pintype "output"))
    )
    (net (code "29") (name "IND_SWITCH") (class "Default")
      (node (ref "U$2") (pin "3") (pinfunction "3_3") (pintype "bidirectional"))
      (node (ref "U7") (pin "3") (pinfunction "V1A_3") (pintype "input"))
    )
    (net (code "30") (name "IND_SWITCH_ISO") (class "Default")
      (node (ref "DSUB3") (pin "1") (pinfunction "1_1") (pintype "passive"))
      (node (ref "JP5") (pin "8") (pinfunction "8_8") (pintype "passive"))
      (node (ref "U7") (pin "14") (pinfunction "VOA_14") (pintype "output"))
    )
    (net (code "31") (name "I{slash}O_UPDATE") (class "Default")
      (node (ref "U$2") (pin "18") (pinfunction "TX1_18_18") (pintype "bidirectional"))
      (node (ref "U1") (pin "1") (pinfunction "I/O_UPDATE_1") (pintype "bidirectional"))
    )
    (net (code "32") (name "Net-(IOUT+-PadTP)") (class "Default")
      (node (ref "IOUT+") (pin "TP") (pinfunction "TP_TP") (pintype "input"))
      (node (ref "JP1") (pin "2") (pinfunction "2_2") (pintype "passive"))
      (node (ref "JP1") (pin "4") (pinfunction "4_4") (pintype "passive"))
      (node (ref "JP1") (pin "6") (pinfunction "6_6") (pintype "passive"))
      (node (ref "R2_H") (pin "2") (pinfunction "2_2") (pintype "passive"))
    )
    (net (code "33") (name "Net-(JP1-Pad1)") (class "Default")
      (node (ref "JP1") (pin "1") (pinfunction "1_1") (pintype "passive"))
      (node (ref "R_HG1") (pin "2") (pinfunction "2_2") (pintype "passive"))
    )
    (net (code "34") (name "Net-(JP1-Pad3)") (class "Default")
      (node (ref "JP1") (pin "3") (pinfunction "3_3") (pintype "passive"))
      (node (ref "R_HG2") (pin "2") (pinfunction "2_2") (pintype "passive"))
    )
    (net (code "35") (name "Net-(JP1-Pad5)") (class "Default")
      (node (ref "JP1") (pin "5") (pinfunction "5_5") (pintype "passive"))
      (node (ref "R_HG3") (pin "2") (pinfunction "2_2") (pintype "passive"))
    )
    (net (code "36") (name "Net-(U1-DACBP)") (class "Default")
      (node (ref "C2") (pin "2") (pinfunction "2_2") (pintype "passive"))
      (node (ref "U1") (pin "23") (pinfunction "DACBP_23") (pintype "input"))
    )
    (net (code "37") (name "Net-(U1-DAC_RSET)") (class "Default")
      (node (ref "R_SET1") (pin "2") (pinfunction "2_2") (pintype "passive"))
      (node (ref "U1") (pin "24") (pinfunction "DAC_RSET_24") (pintype "input"))
    )
    (net (code "38") (name "Net-(U1-IOUT)") (class "Default")
      (node (ref "R4_DAC") (pin "2") (pinfunction "2_2") (pintype "passive"))
      (node (ref "RG_DAC") (pin "1") (pinfunction "1_1") (pintype "passive"))
      (node (ref "RY_DAC") (pin "1") (pinfunction "1_1") (pintype "passive"))
      (node (ref "U1") (pin "21") (pinfunction "IOUT_21") (pintype "output"))
    )
    (net (code "39") (name "Net-(U1-LOOP_FILTER)") (class "Default")
      (node (ref "C38") (pin "2") (pinfunction "2_2") (pintype "passive"))
      (node (ref "U1") (pin "12") (pinfunction "LOOP_FILTER_12") (pintype "input"))
    )
    (net (code "40") (name "Net-(U1-~{IOUT})") (class "Default")
      (node (ref "R1_DAC") (pin "2") (pinfunction "2_2") (pintype "passive"))
      (node (ref "R2_DAC") (pin "2") (pinfunction "2_2") (pintype "passive"))
      (node (ref "RX_DAC") (pin "1") (pinfunction "1_1") (pintype "passive"))
      (node (ref "U1") (pin "20") (pinfunction "~{IOUT}_20") (pintype "output"))
    )
    (net (code "41") (name "Net-(U1-~{OSC{slash}}REFCLK)") (class "Default")
      (node (ref "C1") (pin "2") (pinfunction "2_2") (pintype "passive"))
      (node (ref "U1") (pin "8") (pinfunction "~{OSC/}REFCLK_8") (pintype "input"))
    )
    (net (code "42") (name "Net-(U2-SET)") (class "Default")
      (node (ref "R3") (pin "2") (pinfunction "2_2") (pintype "passive"))
      (node (ref "U2") (pin "3") (pinfunction "SET_3") (pintype "input"))
    )
    (net (code "43") (name "Net-(U6-BOOST)") (class "Default")
      (node (ref "R1") (pin "1") (pinfunction "1_1") (pintype "passive"))
      (node (ref "U6") (pin "1") (pinfunction "BOOST_1") (pintype "input"))
    )
    (net (code "44") (name "Net-(U6-CAP+)") (class "Default")
      (node (ref "C50") (pin "1") (pinfunction "1_1") (pintype "passive"))
      (node (ref "U6") (pin "2") (pinfunction "CAP+_2") (pintype "passive"))
    )
    (net (code "45") (name "Net-(U6-CAP-)") (class "Default")
      (node (ref "C50") (pin "2") (pinfunction "2_2") (pintype "passive"))
      (node (ref "U6") (pin "4") (pinfunction "CAP-_4") (pintype "passive"))
    )
    (net (code "46") (name "PS0") (class "Default")
      (node (ref "U$2") (pin "20") (pinfunction "SDA_20_20") (pintype "bidirectional"))
      (node (ref "U1") (pin "47") (pinfunction "PS0_47") (pintype "input"))
    )
    (net (code "47") (name "PS1") (class "Default")
      (node (ref "U$2") (pin "19") (pinfunction "RX1_19_19") (pintype "bidirectional"))
      (node (ref "U1") (pin "48") (pinfunction "PS1_48") (pintype "input"))
    )
    (net (code "48") (name "REFCLK") (class "Default")
      (node (ref "CLK") (pin "TP") (pinfunction "TP_TP") (pintype "input"))
      (node (ref "U1") (pin "9") (pinfunction "OSC/REFCLK_9") (pintype "input"))
      (node (ref "U2") (pin "5") (pinfunction "OUT_5") (pintype "output"))
    )
    (net (code "49") (name "RESET") (class "Default")
      (node (ref "U$2") (pin "21") (pinfunction "SCL_21_21") (pintype "bidirectional"))
      (node (ref "U1") (pin "36") (pinfunction "RESET_36") (pintype "input"))
    )
    (net (code "50") (name "SCLK") (class "Default")
      (node (ref "SCLK") (pin "TP") (pinfunction "TP_TP") (pintype "input"))
      (node (ref "U$2") (pin "SPCK") (pinfunction "SPCK_SPCK") (pintype "bidirectional"))
      (node (ref "U1") (pin "40") (pinfunction "SCLK_40") (pintype "input"))
    )
    (net (code "51") (name "SDIO") (class "Default")
      (node (ref "SDIO") (pin "TP") (pinfunction "TP_TP") (pintype "input"))
      (node (ref "U$2") (pin "MOSI") (pinfunction "MOSI_MOSI") (pintype "bidirectional"))
      (node (ref "U1") (pin "41") (pinfunction "SDIO_41") (pintype "input"))
    )
    (net (code "52") (name "SDO") (class "Default")
      (node (ref "SDO") (pin "TP") (pinfunction "TP_TP") (pintype "input"))
      (node (ref "U$2") (pin "MISO") (pinfunction "MISO_MISO") (pintype "bidirectional"))
      (node (ref "U1") (pin "38") (pinfunction "SDO_38") (pintype "output"))
    )
    (net (code "53") (name "SW_DIN+") (class "Default")
      (node (ref "DSUB2") (pin "3") (pinfunction "3_3") (pintype "passive"))
      (node (ref "U$2") (pin "10") (pinfunction "10_10") (pintype "bidirectional"))
    )
    (net (code "54") (name "SW_DIN-") (class "Default")
      (node (ref "DSUB2") (pin "7") (pinfunction "7_7") (pintype "passive"))
      (node (ref "U$2") (pin "11") (pinfunction "11_11") (pintype "bidirectional"))
    )
    (net (code "55") (name "SW_RESET") (class "Default")
      (node (ref "DSUB2") (pin "8") (pinfunction "8_8") (pintype "passive"))
      (node (ref "U$2") (pin "9") (pinfunction "9_9") (pintype "bidirectional"))
    )
    (net (code "56") (name "SW_SCLK") (class "Default")
      (node (ref "DSUB2") (pin "2") (pinfunction "2_2") (pintype "passive"))
      (node (ref "U$2") (pin "12") (pinfunction "12_12") (pintype "bidirectional"))
    )
    (net (code "57") (name "SW_SYNC") (class "Default")
      (node (ref "DSUB2") (pin "4") (pinfunction "4_4") (pintype "passive"))
      (node (ref "U$2") (pin "8") (pinfunction "8_8") (pintype "bidirectional"))
    )
    (net (code "58") (name "SW_TEST_1") (class "Default")
      (node (ref "DSUB2") (pin "5") (pinfunction "5_5") (pintype "passive"))
      (node (ref "R10") (pin "2") (pinfunction "2_2") (pintype "passive"))
      (node (ref "U$2") (pin "7") (pinfunction "7_7") (pintype "bidirectional"))
    )
    (net (code "59") (name "SW_TEST_2") (class "Default")
      (node (ref "DSUB2") (pin "1") (pinfunction "1_1") (pintype "passive"))
      (node (ref "R11") (pin "2") (pinfunction "2_2") (pintype "passive"))
      (node (ref "U$2") (pin "13") (pinfunction "13_13") (pintype "bidirectional"))
    )
    (net (code "60") (name "VBAT+") (class "Default")
      (node (ref "JP2") (pin "1") (pinfunction "1_1") (pintype "passive"))
      (node (ref "JP3") (pin "1") (pinfunction "1_1") (pintype "passive"))
      (node (ref "S3") (pin "6") (pinfunction "S1_6") (pintype "passive"))
    )
    (net (code "61") (name "VBAT-") (class "Default")
      (node (ref "JP4") (pin "2") (pinfunction "2_2") (pintype "passive"))
      (node (ref "JP6") (pin "2") (pinfunction "2_2") (pintype "passive"))
      (node (ref "S3") (pin "3") (pinfunction "S_3") (pintype "passive"))
    )
    (net (code "62") (name "VIN_NEG") (class "Default")
      (node (ref "C41") (pin "2") (pinfunction "2_2") (pintype "passive"))
      (node (ref "C42") (pin "2") (pinfunction "2_2") (pintype "passive"))
      (node (ref "IC3") (pin "4") (pinfunction "V-_4") (pintype "power_in"))
      (node (ref "S3") (pin "2") (pinfunction "P_2") (pintype "passive"))
      (node (ref "VIN_NEG") (pin "TP") (pinfunction "TP_TP") (pintype "input"))
    )
    (net (code "63") (name "VIN_POS") (class "Default")
      (node (ref "C39") (pin "2") (pinfunction "2_2") (pintype "passive"))
      (node (ref "C40") (pin "2") (pinfunction "2_2") (pintype "passive"))
      (node (ref "C46") (pin "1") (pinfunction "1_1") (pintype "passive"))
      (node (ref "C48") (pin "1") (pinfunction "1_1") (pintype "passive"))
      (node (ref "IC1") (pin "3") (pinfunction "VIN_3") (pintype "input"))
      (node (ref "IC2") (pin "3") (pinfunction "VIN_3") (pintype "input"))
      (node (ref "IC3") (pin "8") (pinfunction "V+_8") (pintype "power_in"))
      (node (ref "R1") (pin "2") (pinfunction "2_2") (pintype "passive"))
      (node (ref "S3") (pin "5") (pinfunction "P1_5") (pintype "passive"))
      (node (ref "U6") (pin "8") (pinfunction "V+_8") (pintype "power_in"))
      (node (ref "VIN_POS") (pin "TP") (pinfunction "TP_TP") (pintype "input"))
    )
    (net (code "64") (name "V_ISO_INIT") (class "Default")
      (node (ref "C25") (pin "1") (pinfunction "1_1") (pintype "passive"))
      (node (ref "L1") (pin "1") (pinfunction "1_1") (pintype "passive"))
      (node (ref "PS1") (pin "6") (pinfunction "VISO_6") (pintype "bidirectional"))
      (node (ref "PS1") (pin "8") (pinfunction "VSEL_8") (pintype "bidirectional"))
    )
    (net (code "65") (name "V_ISO_TRIG") (class "Default")
      (node (ref "C16") (pin "1") (pinfunction "1_1") (pintype "passive"))
      (node (ref "C17") (pin "1") (pinfunction "1_1") (pintype "passive"))
      (node (ref "C24") (pin "1") (pinfunction "1_1") (pintype "passive"))
      (node (ref "C29") (pin "1") (pinfunction "1_1") (pintype "passive"))
      (node (ref "C30") (pin "1") (pinfunction "1_1") (pintype "passive"))
      (node (ref "L1") (pin "2") (pinfunction "2_2") (pintype "passive"))
      (node (ref "U7") (pin "16") (pinfunction "VDD_16") (pintype "power_in"))
      (node (ref "U8") (pin "16") (pinfunction "VDD_16") (pintype "power_in"))
    )
    (net (code "66") (name "unconnected-(U$2-5V_SPI-Pad5V_2)") (class "Default")
      (node (ref "U$2") (pin "5V_2") (pinfunction "5V_SPI_5V_2") (pintype "bidirectional"))
    )
    (net (code "67") (name "unconnected-(U$2-GND-PadGND_1)") (class "Default")
      (node (ref "U$2") (pin "GND_1") (pinfunction "GND_GND_1") (pintype "bidirectional"))
    )
    (net (code "68") (name "unconnected-(U$2-MASTER_R_SPI-PadMASTER_RESET_SPI)") (class "Default")
      (node (ref "U$2") (pin "MASTER_RESET_SPI") (pinfunction "MASTER_R_SPI_MASTER_RESET_SPI") (pintype "bidirectional"))
    )
    (net (code "69") (name "unconnected-(U$2-NC-PadNC_2)") (class "Default")
      (node (ref "U$2") (pin "NC_2") (pinfunction "NC_NC_2") (pintype "no_connect"))
    )
    (net (code "70") (name "unconnected-(U$2-PadAREF)") (class "Default")
      (node (ref "U$2") (pin "AREF") (pinfunction "AREF_AREF") (pintype "bidirectional"))
    )
    (net (code "71") (name "unconnected-(U$2-PadIOREF)") (class "Default")
      (node (ref "U$2") (pin "IOREF") (pinfunction "IOREF_IOREF") (pintype "bidirectional"))
    )
    (net (code "72") (name "unconnected-(U$2-PadRESET)") (class "Default")
      (node (ref "U$2") (pin "RESET") (pinfunction "RESET_RESET") (pintype "bidirectional"))
    )
    (net (code "73") (name "unconnected-(U$2-PadSCL1)") (class "Default")
      (node (ref "U$2") (pin "SCL1") (pinfunction "SCL1_SCL1") (pintype "bidirectional"))
    )
    (net (code "74") (name "unconnected-(U$2-PadSDA1)") (class "Default")
      (node (ref "U$2") (pin "SDA1") (pinfunction "SDA1_SDA1") (pintype "bidirectional"))
    )
    (net (code "75") (name "unconnected-(U$2-PadVIN)") (class "Default")
      (node (ref "U$2") (pin "VIN") (pinfunction "VIN_VIN") (pintype "bidirectional"))
    )
    (net (code "76") (name "unconnected-(U$2-RX0<0-Pad0)") (class "Default")
      (node (ref "U$2") (pin "0") (pinfunction "RX0<0_0") (pintype "bidirectional"))
    )
    (net (code "77") (name "unconnected-(U$2-TX0>1-Pad1)") (class "Default")
      (node (ref "U$2") (pin "1") (pinfunction "TX0>1_1") (pintype "bidirectional"))
    )
    (net (code "78") (name "unconnected-(U1-COMP_IN-Pad30)") (class "Default")
      (node (ref "U1") (pin "30") (pinfunction "COMP_IN_30") (pintype "input"))
    )
    (net (code "79") (name "unconnected-(U1-COMP_OUT-Pad28)") (class "Default")
      (node (ref "U1") (pin "28") (pinfunction "COMP_OUT_28") (pintype "passive"))
    )
    (net (code "80") (name "unconnected-(U1-CRYSTAL_OUT-Pad10)") (class "Default")
      (node (ref "U1") (pin "10") (pinfunction "CRYSTAL_OUT_10") (pintype "output"))
    )
    (net (code "81") (name "unconnected-(U1-SYNC_CLK-Pad45)") (class "Default")
      (node (ref "U1") (pin "45") (pinfunction "SYNC_CLK_45") (pintype "input"))
    )
    (net (code "82") (name "unconnected-(U1-SYNC_IN-Pad44)") (class "Default")
      (node (ref "U1") (pin "44") (pinfunction "SYNC_IN_44") (pintype "input"))
    )
    (net (code "83") (name "unconnected-(U1-~{COMP_IN}-Pad31)") (class "Default")
      (node (ref "U1") (pin "31") (pinfunction "~{COMP_IN}_31") (pintype "input"))
    )
    (net (code "84") (name "unconnected-(U6-LV-Pad6)") (class "Default")
      (node (ref "U6") (pin "6") (pinfunction "LV_6") (pintype "input"))
    )
    (net (code "85") (name "unconnected-(U6-OSC-Pad7)") (class "Default")
      (node (ref "U6") (pin "7") (pinfunction "OSC_7") (pintype "input"))
    )
    (net (code "86") (name "~{CS}") (class "Default")
      (node (ref "U$2") (pin "17") (pinfunction "RX2_17_17") (pintype "bidirectional"))
      (node (ref "U1") (pin "39") (pinfunction "~{CS}_39") (pintype "input"))
    )
  )
)
